# Sheet3_W5500_2.net
KiCad netlist of a schematic drawn in Altium Designer
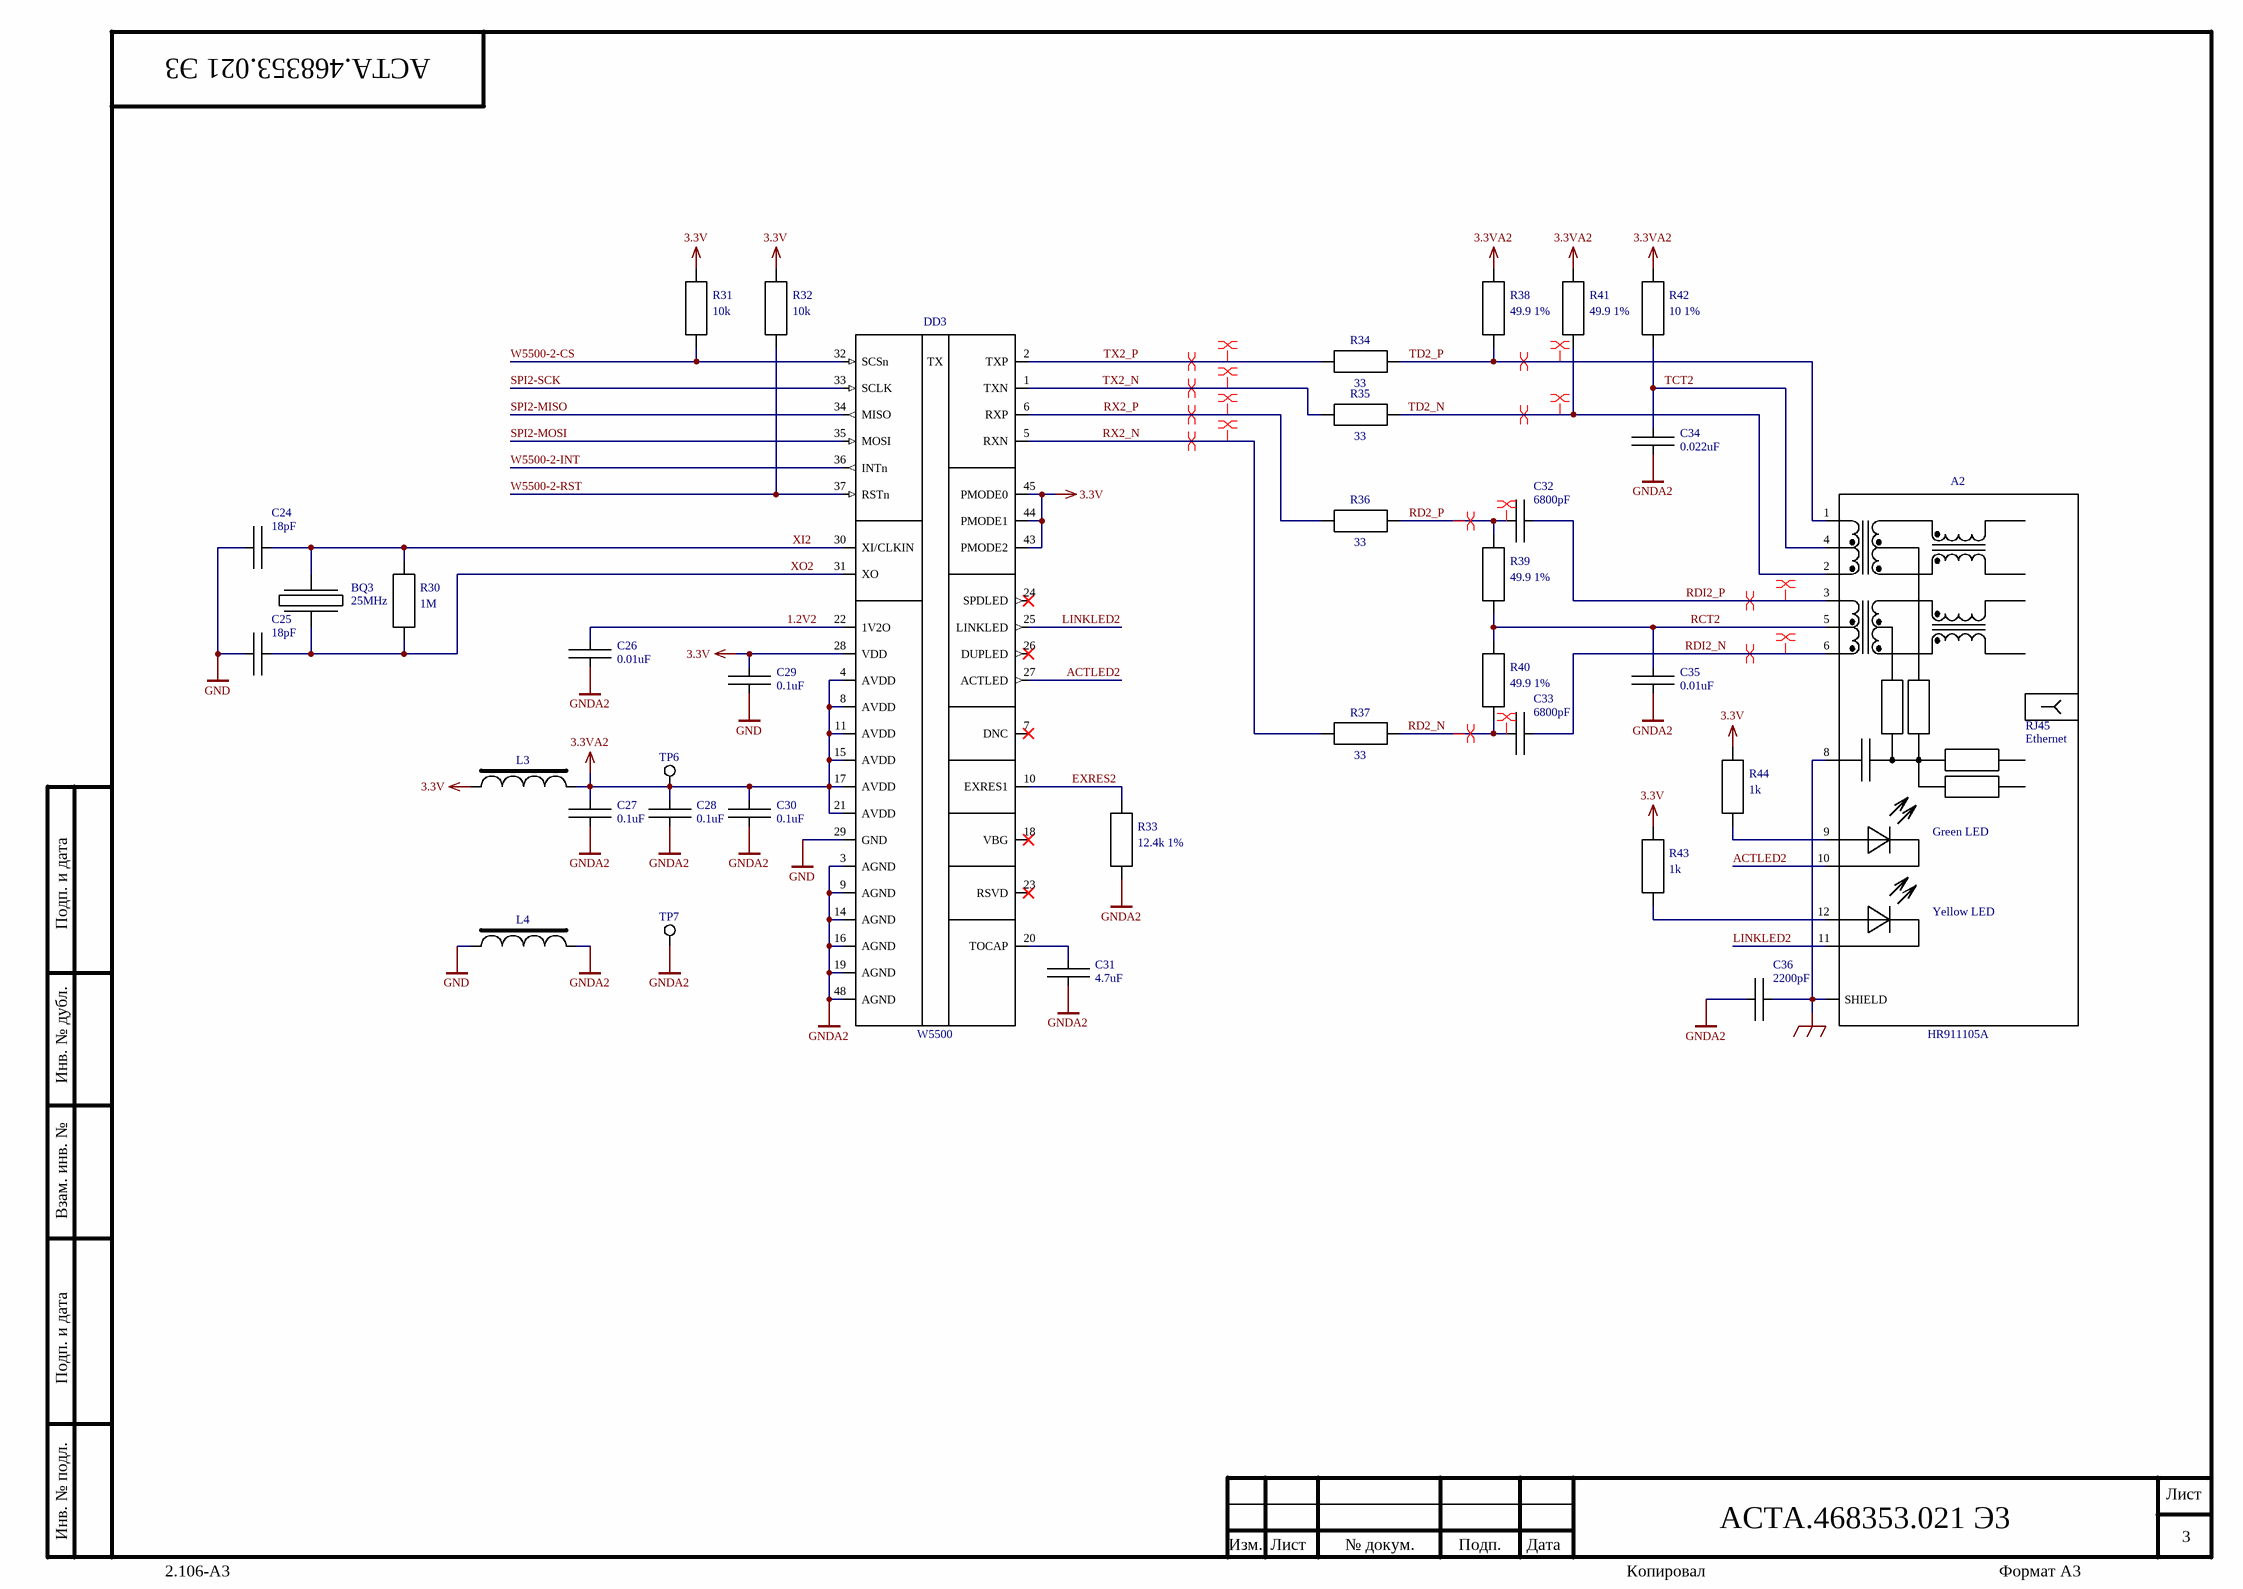
[diagram p0: Sheet3_W5500_2.SchDoc]

(export (version "E")
  (design (tool "Eeschema 10.0.6"))
  (components
    (comp (ref "A2")
      (value "HR911105A")
      (footprint "HR911105A")
      (description "Ethernet Connector 10/100 1x1 Tab Down RJ45 w/mag G/Y LED")
      (libsource (lib "Devices") (part "HR911105A"))
    )
    (comp (ref "BQ3")
      (value "25MHz")
      (footprint "HT-49S")
      (fields (field (name "Comment") "HT-49S_Rated"))
      (libsource (lib "Resonators") (part "HT-49S_Rated"))
    )
    (comp (ref "C24")
      (value "18pF")
      (footprint "CAP0805")
      (fields (field (name "Comment") "CAP0805_Rated"))
      (libsource (lib "Ceramic_Capacitors") (part "CAP0805_Rated"))
    )
    (comp (ref "C25")
      (value "18pF")
      (footprint "CAP0805")
      (fields (field (name "Comment") "CAP0805_Rated"))
      (libsource (lib "Ceramic_Capacitors") (part "CAP0805_Rated"))
    )
    (comp (ref "C26")
      (value "0.01uF")
      (footprint "CAP0805")
      (fields (field (name "Comment") "CAP0805_Rated"))
      (libsource (lib "Ceramic_Capacitors") (part "CAP0805_Rated"))
    )
    (comp (ref "C27")
      (value "0.1uF")
      (footprint "CAP0805")
      (fields (field (name "Comment") "CAP0805_Rated"))
      (libsource (lib "Ceramic_Capacitors") (part "CAP0805_Rated"))
    )
    (comp (ref "C28")
      (value "0.1uF")
      (footprint "CAP0805")
      (fields (field (name "Comment") "CAP0805_Rated"))
      (libsource (lib "Ceramic_Capacitors") (part "CAP0805_Rated"))
    )
    (comp (ref "C29")
      (value "0.1uF")
      (footprint "CAP0805")
      (fields (field (name "Comment") "CAP0805_Rated"))
      (libsource (lib "Ceramic_Capacitors") (part "CAP0805_Rated"))
    )
    (comp (ref "C30")
      (value "0.1uF")
      (footprint "CAP0805")
      (fields (field (name "Comment") "CAP0805_Rated"))
      (libsource (lib "Ceramic_Capacitors") (part "CAP0805_Rated"))
    )
    (comp (ref "C31")
      (value "4.7uF")
      (footprint "CAP1206")
      (fields (field (name "Comment") "CAP1206_Rated"))
      (libsource (lib "Ceramic_Capacitors") (part "CAP1206_Rated"))
    )
    (comp (ref "C32")
      (value "6800pF")
      (footprint "CAP0805")
      (fields (field (name "Comment") "CAP0805_Rated"))
      (libsource (lib "Ceramic_Capacitors") (part "CAP0805_Rated"))
    )
    (comp (ref "C33")
      (value "6800pF")
      (footprint "CAP0805")
      (fields (field (name "Comment") "CAP0805_Rated"))
      (libsource (lib "Ceramic_Capacitors") (part "CAP0805_Rated"))
    )
    (comp (ref "C34")
      (value "0.022uF")
      (footprint "CAP0805")
      (fields (field (name "Comment") "CAP0805_Rated"))
      (libsource (lib "Ceramic_Capacitors") (part "CAP0805_Rated"))
    )
    (comp (ref "C35")
      (value "0.01uF")
      (footprint "CAP0805")
      (fields (field (name "Comment") "CAP0805_Rated"))
      (libsource (lib "Ceramic_Capacitors") (part "CAP0805_Rated"))
    )
    (comp (ref "C36")
      (value "2200pF")
      (footprint "CAP1812")
      (fields (field (name "Comment") "CAP1812_Rated"))
      (libsource (lib "Ceramic_Capacitors") (part "CAP1812_Rated"))
    )
    (comp (ref "DD3")
      (value "W5500")
      (footprint "LQFP-48")
      (description "Ethernet ICs 3in1 Enet Controller TCP/IP +MAC+PHY")
      (libsource (lib "Interface_ICs") (part "W5500"))
    )
    (comp (ref "L3")
      (value "BLM21BD121SN1D")
      (footprint "IND0805")
      (description "Ferrite Bead 0805 120 Ohm")
      (fields (field (name "MANUFACTURER") "Murata") (field (name "TOLERANCE") "25%"))
      (libsource (lib "Inductors") (part "BLM21BD121SN1D"))
    )
    (comp (ref "L4")
      (value "BLM21BD121SN1D")
      (footprint "IND0805")
      (description "Ferrite Bead 0805 120 Ohm")
      (fields (field (name "MANUFACTURER") "Murata") (field (name "TOLERANCE") "25%"))
      (libsource (lib "Inductors") (part "BLM21BD121SN1D"))
    )
    (comp (ref "R30")
      (value "1M")
      (footprint "RES0805")
      (fields (field (name "TOLERANCE") "5%") (field (name "Comment") "RES0805_Rated"))
      (libsource (lib "Resistors") (part "RES0805_Rated"))
    )
    (comp (ref "R31")
      (value "10k")
      (footprint "RES0805")
      (fields (field (name "TOLERANCE") "5%") (field (name "Comment") "RES0805_Rated"))
      (libsource (lib "Resistors") (part "RES0805_Rated"))
    )
    (comp (ref "R32")
      (value "10k")
      (footprint "RES0805")
      (fields (field (name "TOLERANCE") "5%") (field (name "Comment") "RES0805_Rated"))
      (libsource (lib "Resistors") (part "RES0805_Rated"))
    )
    (comp (ref "R33")
      (value "12.4k 1%")
      (footprint "RES0805")
      (fields (field (name "TOLERANCE") "5%") (field (name "Comment") "RES0805_Rated"))
      (libsource (lib "Resistors") (part "RES0805_Rated"))
    )
    (comp (ref "R34")
      (value "33")
      (footprint "RES0805")
      (fields (field (name "TOLERANCE") "5%") (field (name "Comment") "RES0805_Rated"))
      (libsource (lib "") (part "RES0805_Rated_1"))
    )
    (comp (ref "R35")
      (value "33")
      (footprint "RES0805")
      (fields (field (name "TOLERANCE") "5%") (field (name "Comment") "RES0805_Rated"))
      (libsource (lib "") (part "RES0805_Rated_1"))
    )
    (comp (ref "R36")
      (value "33")
      (footprint "RES0805")
      (fields (field (name "TOLERANCE") "5%") (field (name "Comment") "RES0805_Rated"))
      (libsource (lib "") (part "RES0805_Rated_1"))
    )
    (comp (ref "R37")
      (value "33")
      (footprint "RES0805")
      (fields (field (name "TOLERANCE") "5%") (field (name "Comment") "RES0805_Rated"))
      (libsource (lib "") (part "RES0805_Rated_1"))
    )
    (comp (ref "R38")
      (value "49.9 1%")
      (footprint "RES0805")
      (fields (field (name "TOLERANCE") "5%") (field (name "Comment") "RES0805_Rated"))
      (libsource (lib "Resistors") (part "RES0805_Rated"))
    )
    (comp (ref "R39")
      (value "49.9 1%")
      (footprint "RES0805")
      (fields (field (name "TOLERANCE") "5%") (field (name "Comment") "RES0805_Rated"))
      (libsource (lib "Resistors") (part "RES0805_Rated"))
    )
    (comp (ref "R40")
      (value "49.9 1%")
      (footprint "RES0805")
      (fields (field (name "TOLERANCE") "5%") (field (name "Comment") "RES0805_Rated"))
      (libsource (lib "Resistors") (part "RES0805_Rated"))
    )
    (comp (ref "R41")
      (value "49.9 1%")
      (footprint "RES0805")
      (fields (field (name "TOLERANCE") "5%") (field (name "Comment") "RES0805_Rated"))
      (libsource (lib "Resistors") (part "RES0805_Rated"))
    )
    (comp (ref "R42")
      (value "10 1%")
      (footprint "RES0805")
      (fields (field (name "TOLERANCE") "5%") (field (name "Comment") "RES0805_Rated"))
      (libsource (lib "Resistors") (part "RES0805_Rated"))
    )
    (comp (ref "R43")
      (value "1k")
      (footprint "RES0805")
      (fields (field (name "TOLERANCE") "5%") (field (name "Comment") "RES0805_Rated"))
      (libsource (lib "Resistors") (part "RES0805_Rated"))
    )
    (comp (ref "R44")
      (value "1k")
      (footprint "RES0805")
      (fields (field (name "TOLERANCE") "5%") (field (name "Comment") "RES0805_Rated"))
      (libsource (lib "Resistors") (part "RES0805_Rated"))
    )
    (comp (ref "TP6")
      (value "TestPad")
      (footprint "PAD-TH-OCT1x1-0.5")
      (description "TestPoint on PCB")
      (libsource (lib "Connectors") (part "TestPad"))
    )
    (comp (ref "TP7")
      (value "TestPad")
      (footprint "PAD-TH-OCT1x1-0.5")
      (description "TestPoint on PCB")
      (libsource (lib "Connectors") (part "TestPad"))
    )
  )
  (nets
    (net (code "1") (name "/1.2V2") (class "Default")
      (node (ref "C26") (pin "1") (pinfunction "1_1") (pintype "passive"))
      (node (ref "DD3") (pin "22") (pinfunction "1V2O_22") (pintype "power_in"))
    )
    (net (code "2") (name "/ACTLED2") (class "Default")
      (node (ref "A2") (pin "10") (pinfunction "LED1-K_10") (pintype "passive"))
      (node (ref "DD3") (pin "27") (pinfunction "ACTLED_27") (pintype "output"))
    )
    (net (code "3") (name "/EXRES2") (class "Default")
      (node (ref "DD3") (pin "10") (pinfunction "EXRES1_10") (pintype "passive"))
      (node (ref "R33") (pin "2") (pinfunction "2_2") (pintype "passive"))
    )
    (net (code "4") (name "/LINKLED2") (class "Default")
      (node (ref "A2") (pin "11") (pinfunction "LED2-A_11") (pintype "passive"))
      (node (ref "DD3") (pin "25") (pinfunction "LINKLED_25") (pintype "output"))
    )
    (net (code "5") (name "/RCT2") (class "Default")
      (node (ref "A2") (pin "5") (pinfunction "CT_5") (pintype "passive"))
      (node (ref "C35") (pin "1") (pinfunction "1_1") (pintype "passive"))
      (node (ref "R39") (pin "1") (pinfunction "1_1") (pintype "passive"))
      (node (ref "R40") (pin "2") (pinfunction "2_2") (pintype "passive"))
    )
    (net (code "6") (name "/RD2_N") (class "Default")
      (node (ref "C33") (pin "1") (pinfunction "1_1") (pintype "passive"))
      (node (ref "R37") (pin "2") (pinfunction "2_2") (pintype "passive"))
      (node (ref "R40") (pin "1") (pinfunction "1_1") (pintype "passive"))
    )
    (net (code "7") (name "/RD2_P") (class "Default")
      (node (ref "C32") (pin "1") (pinfunction "1_1") (pintype "passive"))
      (node (ref "R36") (pin "2") (pinfunction "2_2") (pintype "passive"))
      (node (ref "R39") (pin "2") (pinfunction "2_2") (pintype "passive"))
    )
    (net (code "8") (name "/RDI2_N") (class "Default")
      (node (ref "A2") (pin "6") (pinfunction "RD-_6") (pintype "passive"))
      (node (ref "C33") (pin "2") (pinfunction "2_2") (pintype "passive"))
    )
    (net (code "9") (name "/RDI2_P") (class "Default")
      (node (ref "A2") (pin "3") (pinfunction "RD+_3") (pintype "passive"))
      (node (ref "C32") (pin "2") (pinfunction "2_2") (pintype "passive"))
    )
    (net (code "10") (name "/RX2_N") (class "Default")
      (node (ref "DD3") (pin "5") (pinfunction "RXN_5") (pintype "passive"))
      (node (ref "R37") (pin "1") (pinfunction "1_1") (pintype "passive"))
    )
    (net (code "11") (name "/RX2_P") (class "Default")
      (node (ref "DD3") (pin "6") (pinfunction "RXP_6") (pintype "passive"))
      (node (ref "R36") (pin "1") (pinfunction "1_1") (pintype "passive"))
    )
    (net (code "12") (name "/SPI2-MISO") (class "Default")
      (node (ref "DD3") (pin "34") (pinfunction "MISO_34") (pintype "output"))
    )
    (net (code "13") (name "/SPI2-MOSI") (class "Default")
      (node (ref "DD3") (pin "35") (pinfunction "MOSI_35") (pintype "input"))
    )
    (net (code "14") (name "/SPI2-SCK") (class "Default")
      (node (ref "DD3") (pin "33") (pinfunction "SCLK_33") (pintype "input"))
    )
    (net (code "15") (name "/TCT2") (class "Default")
      (node (ref "A2") (pin "4") (pinfunction "CT_4") (pintype "passive"))
      (node (ref "C34") (pin "1") (pinfunction "1_1") (pintype "passive"))
      (node (ref "R42") (pin "1") (pinfunction "1_1") (pintype "passive"))
    )
    (net (code "16") (name "/TD2_N") (class "Default")
      (node (ref "A2") (pin "2") (pinfunction "TD-_2") (pintype "passive"))
      (node (ref "R35") (pin "2") (pinfunction "2_2") (pintype "passive"))
      (node (ref "R41") (pin "1") (pinfunction "1_1") (pintype "passive"))
    )
    (net (code "17") (name "/TD2_P") (class "Default")
      (node (ref "A2") (pin "1") (pinfunction "TD+_1") (pintype "passive"))
      (node (ref "R34") (pin "2") (pinfunction "2_2") (pintype "passive"))
      (node (ref "R38") (pin "1") (pinfunction "1_1") (pintype "passive"))
    )
    (net (code "18") (name "/TX2_N") (class "Default")
      (node (ref "DD3") (pin "1") (pinfunction "TXN_1") (pintype "passive"))
      (node (ref "R35") (pin "1") (pinfunction "1_1") (pintype "passive"))
    )
    (net (code "19") (name "/TX2_P") (class "Default")
      (node (ref "DD3") (pin "2") (pinfunction "TXP_2") (pintype "passive"))
      (node (ref "R34") (pin "1") (pinfunction "1_1") (pintype "passive"))
    )
    (net (code "20") (name "/W5500-2-CS") (class "Default")
      (node (ref "DD3") (pin "32") (pinfunction "SCSn_32") (pintype "input"))
      (node (ref "R31") (pin "1") (pinfunction "1_1") (pintype "passive"))
    )
    (net (code "21") (name "/W5500-2-INT") (class "Default")
      (node (ref "DD3") (pin "36") (pinfunction "INTn_36") (pintype "output"))
    )
    (net (code "22") (name "/W5500-2-RST") (class "Default")
      (node (ref "DD3") (pin "37") (pinfunction "RSTn_37") (pintype "input"))
      (node (ref "R32") (pin "1") (pinfunction "1_1") (pintype "passive"))
    )
    (net (code "23") (name "/XI2") (class "Default")
      (node (ref "BQ3") (pin "1") (pinfunction "1_1") (pintype "passive"))
      (node (ref "C24") (pin "2") (pinfunction "2_2") (pintype "passive"))
      (node (ref "DD3") (pin "30") (pinfunction "XI/CLKIN_30") (pintype "passive"))
      (node (ref "R30") (pin "2") (pinfunction "2_2") (pintype "passive"))
    )
    (net (code "24") (name "/XO2") (class "Default")
      (node (ref "BQ3") (pin "2") (pinfunction "2_2") (pintype "passive"))
      (node (ref "C25") (pin "2") (pinfunction "2_2") (pintype "passive"))
      (node (ref "DD3") (pin "31") (pinfunction "XO_31") (pintype "passive"))
      (node (ref "R30") (pin "1") (pinfunction "1_1") (pintype "passive"))
    )
    (net (code "25") (name "3.3V") (class "Default")
      (node (ref "C29") (pin "1") (pinfunction "1_1") (pintype "passive"))
      (node (ref "DD3") (pin "28") (pinfunction "VDD_28") (pintype "power_in"))
      (node (ref "DD3") (pin "43") (pinfunction "PMODE2_43") (pintype "passive"))
      (node (ref "DD3") (pin "44") (pinfunction "PMODE1_44") (pintype "passive"))
      (node (ref "DD3") (pin "45") (pinfunction "PMODE0_45") (pintype "passive"))
      (node (ref "L3") (pin "1") (pinfunction "1_1") (pintype "passive"))
      (node (ref "R31") (pin "2") (pinfunction "2_2") (pintype "passive"))
      (node (ref "R32") (pin "2") (pinfunction "2_2") (pintype "passive"))
      (node (ref "R43") (pin "2") (pinfunction "2_2") (pintype "passive"))
      (node (ref "R44") (pin "2") (pinfunction "2_2") (pintype "passive"))
    )
    (net (code "26") (name "3.3VA2") (class "Default")
      (node (ref "C27") (pin "1") (pinfunction "1_1") (pintype "passive"))
      (node (ref "C28") (pin "1") (pinfunction "1_1") (pintype "passive"))
      (node (ref "C30") (pin "1") (pinfunction "1_1") (pintype "passive"))
      (node (ref "DD3") (pin "11") (pinfunction "AVDD_11") (pintype "power_in"))
      (node (ref "DD3") (pin "15") (pinfunction "AVDD_15") (pintype "power_in"))
      (node (ref "DD3") (pin "17") (pinfunction "AVDD_17") (pintype "power_in"))
      (node (ref "DD3") (pin "21") (pinfunction "AVDD_21") (pintype "power_in"))
      (node (ref "DD3") (pin "4") (pinfunction "AVDD_4") (pintype "power_in"))
      (node (ref "DD3") (pin "8") (pinfunction "AVDD_8") (pintype "power_in"))
      (node (ref "L3") (pin "2") (pinfunction "2_2") (pintype "passive"))
      (node (ref "R38") (pin "2") (pinfunction "2_2") (pintype "passive"))
      (node (ref "R41") (pin "2") (pinfunction "2_2") (pintype "passive"))
      (node (ref "R42") (pin "2") (pinfunction "2_2") (pintype "passive"))
      (node (ref "TP6") (pin "1") (pinfunction "1_1") (pintype "passive"))
    )
    (net (code "27") (name "EARTH") (class "Default")
      (node (ref "A2") (pin "8") (pinfunction "GND_8") (pintype "power_in"))
      (node (ref "A2") (pin "SHIELD") (pinfunction "SHIELD_SHIELD") (pintype "passive"))
      (node (ref "C36") (pin "2") (pinfunction "2_2") (pintype "passive"))
    )
    (net (code "28") (name "GND") (class "Default")
      (node (ref "C24") (pin "1") (pinfunction "1_1") (pintype "passive"))
      (node (ref "C25") (pin "1") (pinfunction "1_1") (pintype "passive"))
      (node (ref "C29") (pin "2") (pinfunction "2_2") (pintype "passive"))
      (node (ref "DD3") (pin "29") (pinfunction "GND_29") (pintype "power_in"))
      (node (ref "L4") (pin "1") (pinfunction "1_1") (pintype "passive"))
    )
    (net (code "29") (name "GNDA2") (class "Default")
      (node (ref "C26") (pin "2") (pinfunction "2_2") (pintype "passive"))
      (node (ref "C27") (pin "2") (pinfunction "2_2") (pintype "passive"))
      (node (ref "C28") (pin "2") (pinfunction "2_2") (pintype "passive"))
      (node (ref "C30") (pin "2") (pinfunction "2_2") (pintype "passive"))
      (node (ref "C31") (pin "2") (pinfunction "2_2") (pintype "passive"))
      (node (ref "C34") (pin "2") (pinfunction "2_2") (pintype "passive"))
      (node (ref "C35") (pin "2") (pinfunction "2_2") (pintype "passive"))
      (node (ref "C36") (pin "1") (pinfunction "1_1") (pintype "passive"))
      (node (ref "DD3") (pin "14") (pinfunction "AGND_14") (pintype "power_in"))
      (node (ref "DD3") (pin "16") (pinfunction "AGND_16") (pintype "power_in"))
      (node (ref "DD3") (pin "19") (pinfunction "AGND_19") (pintype "power_in"))
      (node (ref "DD3") (pin "3") (pinfunction "AGND_3") (pintype "power_in"))
      (node (ref "DD3") (pin "48") (pinfunction "AGND_48") (pintype "power_in"))
      (node (ref "DD3") (pin "9") (pinfunction "AGND_9") (pintype "power_in"))
      (node (ref "L4") (pin "2") (pinfunction "2_2") (pintype "passive"))
      (node (ref "R33") (pin "1") (pinfunction "1_1") (pintype "passive"))
      (node (ref "TP7") (pin "1") (pinfunction "1_1") (pintype "passive"))
    )
    (net (code "30") (name "Net-(A2-LED1-A)") (class "Default")
      (node (ref "A2") (pin "9") (pinfunction "LED1-A_9") (pintype "passive"))
      (node (ref "R44") (pin "1") (pinfunction "1_1") (pintype "passive"))
    )
    (net (code "31") (name "Net-(A2-LED2-K)") (class "Default")
      (node (ref "A2") (pin "12") (pinfunction "LED2-K_12") (pintype "passive"))
      (node (ref "R43") (pin "1") (pinfunction "1_1") (pintype "passive"))
    )
    (net (code "32") (name "Net-(DD3-TOCAP)") (class "Default")
      (node (ref "C31") (pin "1") (pinfunction "1_1") (pintype "passive"))
      (node (ref "DD3") (pin "20") (pinfunction "TOCAP_20") (pintype "passive"))
    )
    (net (code "33") (name "unconnected-(DD3-DNC-Pad7)") (class "Default")
      (node (ref "DD3") (pin "7") (pinfunction "DNC_7") (pintype "passive+no_connect"))
    )
    (net (code "34") (name "unconnected-(DD3-DUPLED-Pad26)") (class "Default")
      (node (ref "DD3") (pin "26") (pinfunction "DUPLED_26") (pintype "output+no_connect"))
    )
    (net (code "35") (name "unconnected-(DD3-RSVD-Pad23)") (class "Default")
      (node (ref "DD3") (pin "23") (pinfunction "RSVD_23") (pintype "passive+no_connect"))
    )
    (net (code "36") (name "unconnected-(DD3-SPDLED-Pad24)") (class "Default")
      (node (ref "DD3") (pin "24") (pinfunction "SPDLED_24") (pintype "output+no_connect"))
    )
    (net (code "37") (name "unconnected-(DD3-VBG-Pad18)") (class "Default")
      (node (ref "DD3") (pin "18") (pinfunction "VBG_18") (pintype "passive+no_connect"))
    )
  )
)
